# p0b-001.net
KiCad netlist of a schematic drawn in EAGLE
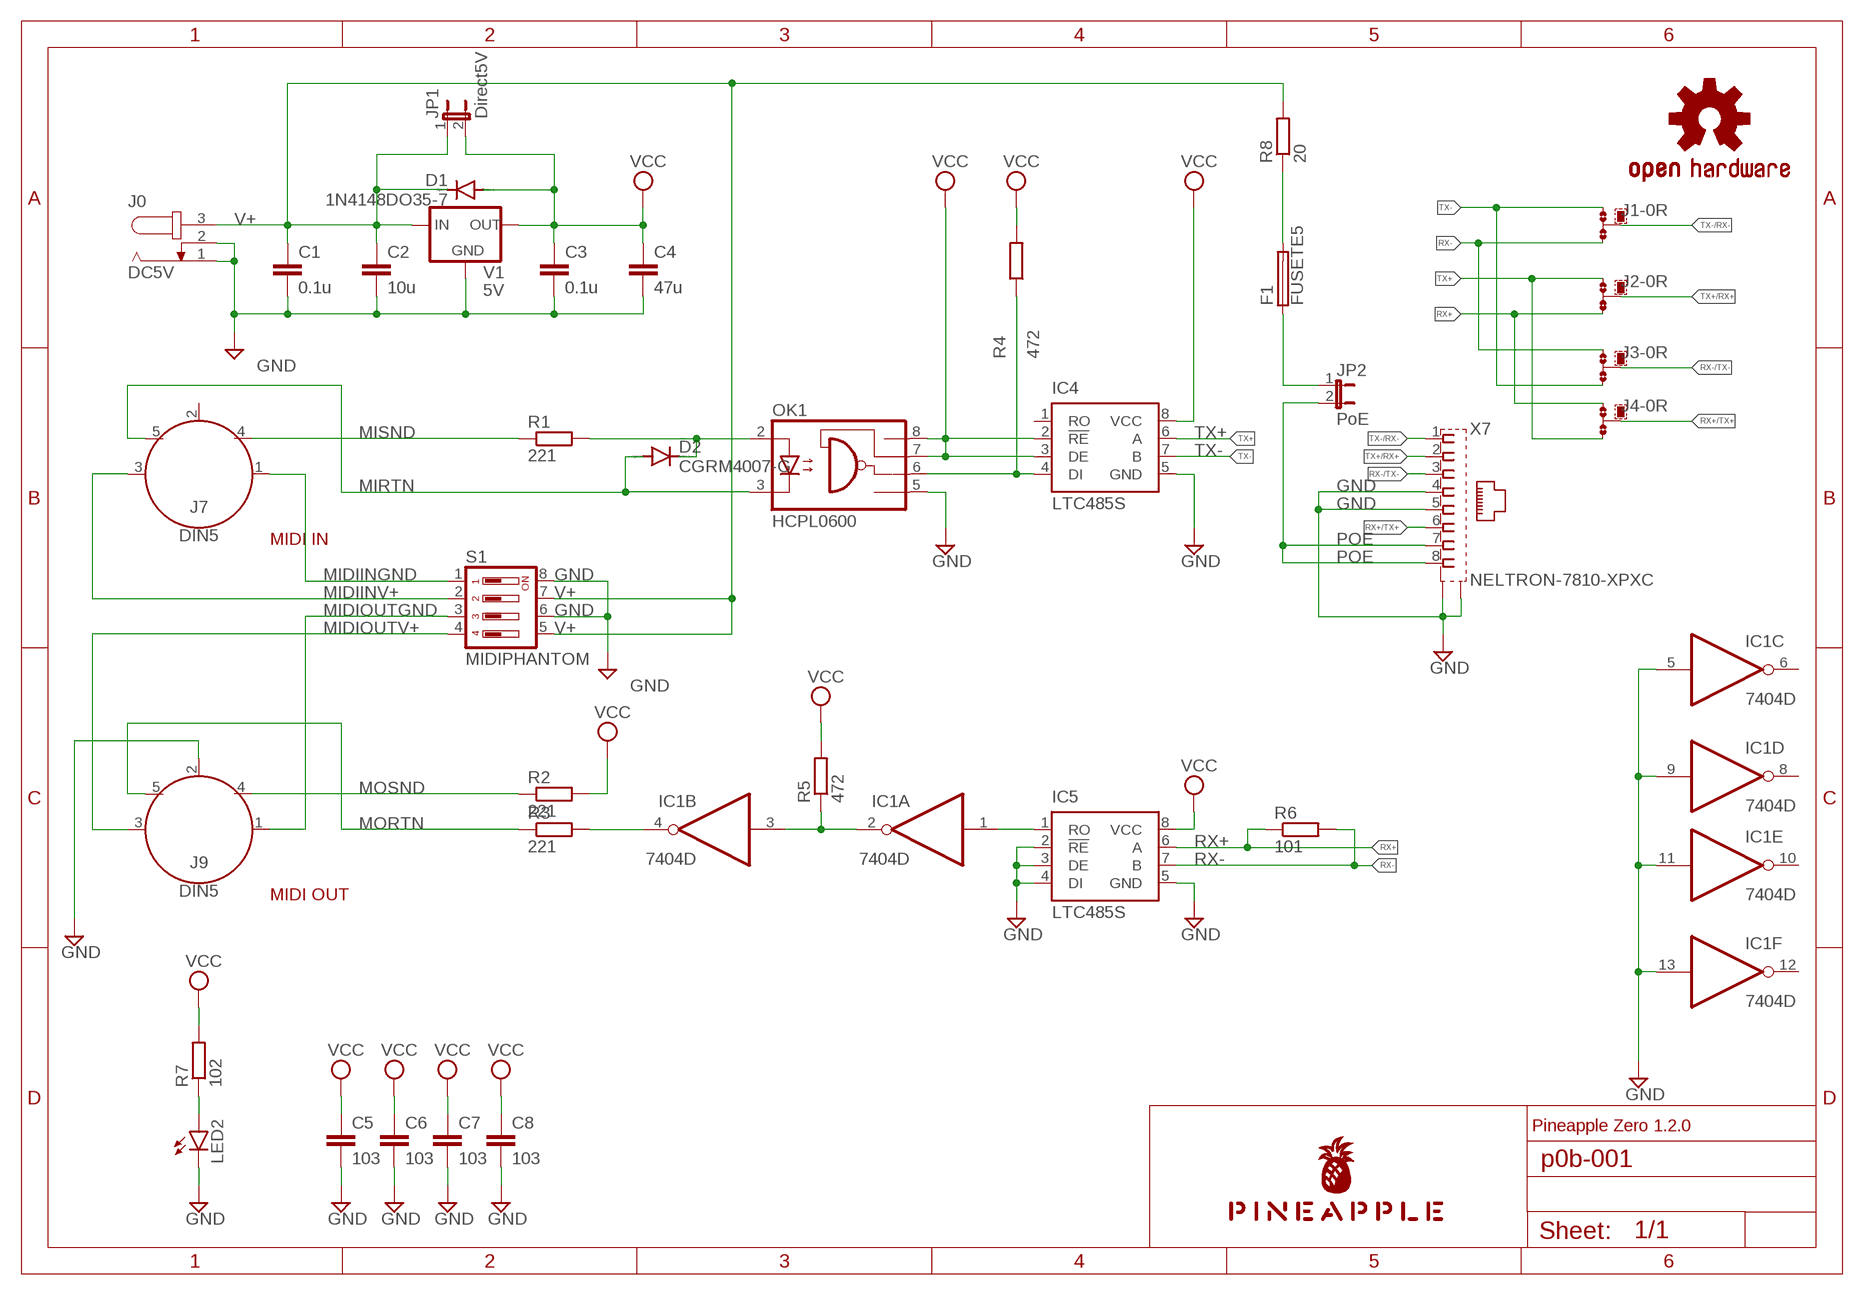
[diagram p0: schematic, sheet 1]

(export (version "E")
  (design (tool "Eeschema 10.0.6"))
  (components
    (comp (ref "C1")
      (value "0.1u")
      (footprint "eagle-import:C025-025X050")
      (libsource (lib "eagle-import") (part "C-EU025-025X050"))
    )
    (comp (ref "C2")
      (value "10u")
      (footprint "eagle-import:C025-030X050")
      (libsource (lib "eagle-import") (part "C-EU025-030X050"))
    )
    (comp (ref "C3")
      (value "0.1u")
      (footprint "eagle-import:C025-025X050")
      (libsource (lib "eagle-import") (part "C-EU025-025X050"))
    )
    (comp (ref "C4")
      (value "47u")
      (footprint "eagle-import:C025-050X050")
      (libsource (lib "eagle-import") (part "C-EU025-050X050"))
    )
    (comp (ref "C5")
      (value "103")
      (footprint "eagle-import:C1206")
      (libsource (lib "eagle-import") (part "C-EUC1206"))
    )
    (comp (ref "C6")
      (value "103")
      (footprint "eagle-import:C1206")
      (libsource (lib "eagle-import") (part "C-EUC1206"))
    )
    (comp (ref "C7")
      (value "103")
      (footprint "eagle-import:C1206")
      (libsource (lib "eagle-import") (part "C-EUC1206"))
    )
    (comp (ref "C8")
      (value "103")
      (footprint "eagle-import:C1206")
      (libsource (lib "eagle-import") (part "C-EUC1206"))
    )
    (comp (ref "D1")
      (value "1N4148DO35-7")
      (footprint "eagle-import:DO35-7")
      (libsource (lib "eagle-import") (part "1N4148DO35-7"))
    )
    (comp (ref "D2")
      (value "CGRM4007-G")
      (footprint "eagle-import:SOD-123_MINI-SMA")
      (libsource (lib "eagle-import") (part "CGRM400-G7"))
    )
    (comp (ref "F1")
      (value "FUSETE5")
      (footprint "eagle-import:TE5")
      (libsource (lib "eagle-import") (part "FUSETE5"))
    )
    (comp (ref "IC1")
      (value "7404D")
      (footprint "eagle-import:SO14")
      (libsource (lib "eagle-import") (part "7404D"))
    )
    (comp (ref "IC4")
      (value "LTC485S")
      (footprint "eagle-import:SOIC8")
      (libsource (lib "eagle-import") (part "LTC485S"))
    )
    (comp (ref "IC5")
      (value "LTC485S")
      (footprint "eagle-import:SOIC8")
      (libsource (lib "eagle-import") (part "LTC485S"))
    )
    (comp (ref "J0")
      (value "DC5V")
      (footprint "eagle-import:SPC4077")
      (libsource (lib "eagle-import") (part "JACK-PLUG0"))
    )
    (comp (ref "J1")
      (value "0R-JUMPA")
      (footprint "eagle-import:A0R-JMP")
      (libsource (lib "eagle-import") (part "0R-JUMPA"))
    )
    (comp (ref "J2")
      (value "0R-JUMPA")
      (footprint "eagle-import:A0R-JMP")
      (libsource (lib "eagle-import") (part "0R-JUMPA"))
    )
    (comp (ref "J3")
      (value "0R-JUMPA")
      (footprint "eagle-import:A0R-JMP")
      (libsource (lib "eagle-import") (part "0R-JUMPA"))
    )
    (comp (ref "J4")
      (value "0R-JUMPA")
      (footprint "eagle-import:A0R-JMP")
      (libsource (lib "eagle-import") (part "0R-JUMPA"))
    )
    (comp (ref "J7")
      (value "DIN5")
      (footprint "eagle-import:DIN5-RA-PTH")
      (libsource (lib "eagle-import") (part "DIN5"))
    )
    (comp (ref "J9")
      (value "DIN5")
      (footprint "eagle-import:DIN5-RA-PTH")
      (libsource (lib "eagle-import") (part "DIN5"))
    )
    (comp (ref "JP1")
      (value "Direct5V")
      (footprint "eagle-import:JP1")
      (libsource (lib "eagle-import") (part "JP1E"))
    )
    (comp (ref "JP2")
      (value "PoE")
      (footprint "eagle-import:JP1")
      (libsource (lib "eagle-import") (part "JP1E"))
    )
    (comp (ref "LED2")
      (value "LEDCHIPLED_1206")
      (footprint "eagle-import:CHIPLED_1206")
      (libsource (lib "eagle-import") (part "LEDCHIPLED_1206"))
    )
    (comp (ref "LOGO1")
      (value "OSHW-LOGOS-COPPER")
      (footprint "eagle-import:OSHW-LOGO-S_COPPER")
      (libsource (lib "eagle-import") (part "OSHW-LOGOS-COPPER"))
    )
    (comp (ref "OK1")
      (value "HCPL0600")
      (footprint "eagle-import:SOIC08")
      (fields (field (name "MF") "AGILENT TECHNOLOGIES") (field (name "MPN") "HCPL-0600-000E"))
      (libsource (lib "eagle-import") (part "HCPL0600"))
    )
    (comp (ref "R1")
      (value "221")
      (footprint "eagle-import:M2012")
      (libsource (lib "eagle-import") (part "R-EU_M2012"))
    )
    (comp (ref "R2")
      (value "221")
      (footprint "eagle-import:M2012")
      (libsource (lib "eagle-import") (part "R-EU_M2012"))
    )
    (comp (ref "R3")
      (value "221")
      (footprint "eagle-import:M2012")
      (libsource (lib "eagle-import") (part "R-EU_M2012"))
    )
    (comp (ref "R4")
      (value "472")
      (footprint "eagle-import:M2012")
      (libsource (lib "eagle-import") (part "R-EU_M2012"))
    )
    (comp (ref "R5")
      (value "472")
      (footprint "eagle-import:M2012")
      (libsource (lib "eagle-import") (part "R-EU_M2012"))
    )
    (comp (ref "R6")
      (value "101")
      (footprint "eagle-import:M2012")
      (libsource (lib "eagle-import") (part "R-EU_M2012"))
    )
    (comp (ref "R7")
      (value "102")
      (footprint "eagle-import:M2012")
      (libsource (lib "eagle-import") (part "R-EU_M2012"))
    )
    (comp (ref "R8")
      (value "20")
      (footprint "eagle-import:0204_5")
      (libsource (lib "eagle-import") (part "R-EU_0204/5"))
    )
    (comp (ref "S1")
      (value "MIDIPHANTOM")
      (footprint "eagle-import:DIP04YL")
      (libsource (lib "eagle-import") (part "DIP04YL"))
    )
    (comp (ref "U$1")
      (value "PINEAPPLE450")
      (footprint "eagle-import:PINEAPPLE450")
      (libsource (lib "eagle-import") (part "PINEAPPLE450"))
    )
    (comp (ref "V1")
      (value "5V")
      (footprint "eagle-import:78XXS")
      (libsource (lib "eagle-import") (part "78XXS"))
    )
    (comp (ref "X7")
      (value "NELTRON-7810-XPXC")
      (footprint "eagle-import:NELTRON-7810-XPXC-FOOTPRINT")
      (libsource (lib "eagle-import") (part "NELTRON-7810-XPXC"))
    )
  )
  (nets
    (net (code "1") (name "/MIDIINGND") (class "Default")
      (node (ref "J7") (pin "1") (pinfunction "1_1") (pintype "bidirectional"))
      (node (ref "S1") (pin "1") (pinfunction "1_1") (pintype "passive"))
    )
    (net (code "2") (name "/MIDIINV+") (class "Default")
      (node (ref "J7") (pin "3") (pinfunction "3_3") (pintype "bidirectional"))
      (node (ref "S1") (pin "2") (pinfunction "2_2") (pintype "passive"))
    )
    (net (code "3") (name "/MIDIOUTGND") (class "Default")
      (node (ref "J9") (pin "1") (pinfunction "1_1") (pintype "bidirectional"))
      (node (ref "S1") (pin "3") (pinfunction "3_3") (pintype "passive"))
    )
    (net (code "4") (name "/MIDIOUTV+") (class "Default")
      (node (ref "J9") (pin "3") (pinfunction "3_3") (pintype "bidirectional"))
      (node (ref "S1") (pin "4") (pinfunction "4_4") (pintype "passive"))
    )
    (net (code "5") (name "/MIRTN") (class "Default")
      (node (ref "D2") (pin "A") (pinfunction "A_A") (pintype "passive"))
      (node (ref "J7") (pin "5") (pinfunction "5_5") (pintype "bidirectional"))
      (node (ref "OK1") (pin "3") (pinfunction "C_3") (pintype "passive"))
    )
    (net (code "6") (name "/MISND") (class "Default")
      (node (ref "J7") (pin "4") (pinfunction "4_4") (pintype "bidirectional"))
      (node (ref "R1") (pin "1") (pinfunction "1_1") (pintype "passive"))
    )
    (net (code "7") (name "/MORTN") (class "Default")
      (node (ref "J9") (pin "5") (pinfunction "5_5") (pintype "bidirectional"))
      (node (ref "R3") (pin "1") (pinfunction "1_1") (pintype "passive"))
    )
    (net (code "8") (name "/MOSND") (class "Default")
      (node (ref "J9") (pin "4") (pinfunction "4_4") (pintype "bidirectional"))
      (node (ref "R2") (pin "1") (pinfunction "1_1") (pintype "passive"))
    )
    (net (code "9") (name "/POE") (class "Default")
      (node (ref "JP2") (pin "2") (pinfunction "2_2") (pintype "passive"))
      (node (ref "X7") (pin "7") (pinfunction "7_7") (pintype "passive"))
      (node (ref "X7") (pin "8") (pinfunction "8_8") (pintype "passive"))
    )
    (net (code "10") (name "/V+") (class "Default")
      (node (ref "C1") (pin "1") (pinfunction "1_1") (pintype "passive"))
      (node (ref "C2") (pin "1") (pinfunction "1_1") (pintype "passive"))
      (node (ref "D1") (pin "C") (pinfunction "C_C") (pintype "passive"))
      (node (ref "J0") (pin "3") (pinfunction "3_3") (pintype "passive"))
      (node (ref "JP1") (pin "1") (pinfunction "1_1") (pintype "passive"))
      (node (ref "R8") (pin "2") (pinfunction "2_2") (pintype "passive"))
      (node (ref "S1") (pin "5") (pinfunction "5_5") (pintype "passive"))
      (node (ref "S1") (pin "7") (pinfunction "7_7") (pintype "passive"))
      (node (ref "V1") (pin "IN") (pinfunction "IN_IN") (pintype "input"))
    )
    (net (code "11") (name "GND") (class "Default")
      (node (ref "C1") (pin "2") (pinfunction "2_2") (pintype "passive"))
      (node (ref "C2") (pin "2") (pinfunction "2_2") (pintype "passive"))
      (node (ref "C3") (pin "2") (pinfunction "2_2") (pintype "passive"))
      (node (ref "C4") (pin "2") (pinfunction "2_2") (pintype "passive"))
      (node (ref "C5") (pin "2") (pinfunction "2_2") (pintype "passive"))
      (node (ref "C6") (pin "2") (pinfunction "2_2") (pintype "passive"))
      (node (ref "C7") (pin "2") (pinfunction "2_2") (pintype "passive"))
      (node (ref "C8") (pin "2") (pinfunction "2_2") (pintype "passive"))
      (node (ref "IC1") (pin "11") (pinfunction "I_11") (pintype "input"))
      (node (ref "IC1") (pin "13") (pinfunction "I_13") (pintype "input"))
      (node (ref "IC1") (pin "5") (pinfunction "I_5") (pintype "input"))
      (node (ref "IC1") (pin "9") (pinfunction "I_9") (pintype "input"))
      (node (ref "IC4") (pin "5") (pinfunction "GND_5") (pintype "input"))
      (node (ref "IC5") (pin "2") (pinfunction "~{RE}_2") (pintype "input"))
      (node (ref "IC5") (pin "3") (pinfunction "DE_3") (pintype "input"))
      (node (ref "IC5") (pin "4") (pinfunction "DI_4") (pintype "input"))
      (node (ref "IC5") (pin "5") (pinfunction "GND_5") (pintype "input"))
      (node (ref "J0") (pin "1") (pinfunction "1_1") (pintype "passive"))
      (node (ref "J0") (pin "2") (pinfunction "2_2") (pintype "passive"))
      (node (ref "J9") (pin "2") (pinfunction "2_2") (pintype "bidirectional"))
      (node (ref "LED2") (pin "C") (pinfunction "C_C") (pintype "passive"))
      (node (ref "OK1") (pin "5") (pinfunction "GND_5") (pintype "passive"))
      (node (ref "S1") (pin "6") (pinfunction "6_6") (pintype "passive"))
      (node (ref "S1") (pin "8") (pinfunction "8_8") (pintype "passive"))
      (node (ref "V1") (pin "GND") (pinfunction "GND_GND") (pintype "input"))
      (node (ref "X7") (pin "4") (pinfunction "4_4") (pintype "passive"))
      (node (ref "X7") (pin "5") (pinfunction "5_5") (pintype "passive"))
      (node (ref "X7") (pin "S1") (pinfunction "S1_S1") (pintype "passive"))
      (node (ref "X7") (pin "S2") (pinfunction "S2_S2") (pintype "passive"))
    )
    (net (code "12") (name "Net-(F1-Pad1)") (class "Default")
      (node (ref "F1") (pin "1") (pinfunction "1_1") (pintype "passive"))
      (node (ref "JP2") (pin "1") (pinfunction "1_1") (pintype "passive"))
    )
    (net (code "13") (name "Net-(F1-Pad2)") (class "Default")
      (node (ref "F1") (pin "2") (pinfunction "2_2") (pintype "passive"))
      (node (ref "R8") (pin "1") (pinfunction "1_1") (pintype "passive"))
    )
    (net (code "14") (name "Net-(IC1A-I)") (class "Default")
      (node (ref "IC1") (pin "1") (pinfunction "I_1") (pintype "input"))
      (node (ref "IC5") (pin "1") (pinfunction "RO_1") (pintype "output"))
    )
    (net (code "15") (name "Net-(IC1A-O)") (class "Default")
      (node (ref "IC1") (pin "2") (pinfunction "O_2") (pintype "output"))
      (node (ref "IC1") (pin "3") (pinfunction "I_3") (pintype "input"))
      (node (ref "R5") (pin "1") (pinfunction "1_1") (pintype "passive"))
    )
    (net (code "16") (name "Net-(IC1B-O)") (class "Default")
      (node (ref "IC1") (pin "4") (pinfunction "O_4") (pintype "output"))
      (node (ref "R3") (pin "2") (pinfunction "2_2") (pintype "passive"))
    )
    (net (code "17") (name "Net-(IC4-DI)") (class "Default")
      (node (ref "IC4") (pin "4") (pinfunction "DI_4") (pintype "input"))
      (node (ref "OK1") (pin "6") (pinfunction "VO_6") (pintype "passive"))
      (node (ref "R4") (pin "1") (pinfunction "1_1") (pintype "passive"))
    )
    (net (code "18") (name "Net-(LED2-PadA)") (class "Default")
      (node (ref "LED2") (pin "A") (pinfunction "A_A") (pintype "passive"))
      (node (ref "R7") (pin "1") (pinfunction "1_1") (pintype "passive"))
    )
    (net (code "19") (name "Net-(OK1-A)") (class "Default")
      (node (ref "D2") (pin "C") (pinfunction "C_C") (pintype "passive"))
      (node (ref "OK1") (pin "2") (pinfunction "A_2") (pintype "passive"))
      (node (ref "R1") (pin "2") (pinfunction "2_2") (pintype "passive"))
    )
    (net (code "20") (name "RX+") (class "Default")
      (node (ref "IC5") (pin "6") (pinfunction "A_6") (pintype "bidirectional"))
      (node (ref "J2") (pin "3") (pinfunction "3_3") (pintype "passive"))
      (node (ref "J4") (pin "1") (pinfunction "1_1") (pintype "passive"))
      (node (ref "R6") (pin "1") (pinfunction "1_1") (pintype "passive"))
    )
    (net (code "21") (name "RX+{slash}TX+") (class "Default")
      (node (ref "J4") (pin "2") (pinfunction "2_2") (pintype "passive"))
      (node (ref "X7") (pin "6") (pinfunction "6_6") (pintype "passive"))
    )
    (net (code "22") (name "RX-") (class "Default")
      (node (ref "IC5") (pin "7") (pinfunction "B_7") (pintype "bidirectional"))
      (node (ref "J1") (pin "3") (pinfunction "3_3") (pintype "passive"))
      (node (ref "J3") (pin "1") (pinfunction "1_1") (pintype "passive"))
      (node (ref "R6") (pin "2") (pinfunction "2_2") (pintype "passive"))
    )
    (net (code "23") (name "RX-{slash}TX-") (class "Default")
      (node (ref "J3") (pin "2") (pinfunction "2_2") (pintype "passive"))
      (node (ref "X7") (pin "3") (pinfunction "3_3") (pintype "passive"))
    )
    (net (code "24") (name "TX+") (class "Default")
      (node (ref "IC4") (pin "6") (pinfunction "A_6") (pintype "bidirectional"))
      (node (ref "J2") (pin "1") (pinfunction "1_1") (pintype "passive"))
      (node (ref "J4") (pin "3") (pinfunction "3_3") (pintype "passive"))
    )
    (net (code "25") (name "TX+{slash}RX+") (class "Default")
      (node (ref "J2") (pin "2") (pinfunction "2_2") (pintype "passive"))
      (node (ref "X7") (pin "2") (pinfunction "2_2") (pintype "passive"))
    )
    (net (code "26") (name "TX-") (class "Default")
      (node (ref "IC4") (pin "7") (pinfunction "B_7") (pintype "bidirectional"))
      (node (ref "J1") (pin "1") (pinfunction "1_1") (pintype "passive"))
      (node (ref "J3") (pin "3") (pinfunction "3_3") (pintype "passive"))
    )
    (net (code "27") (name "TX-{slash}RX-") (class "Default")
      (node (ref "J1") (pin "2") (pinfunction "2_2") (pintype "passive"))
      (node (ref "X7") (pin "1") (pinfunction "1_1") (pintype "passive"))
    )
    (net (code "28") (name "VCC") (class "Default")
      (node (ref "C3") (pin "1") (pinfunction "1_1") (pintype "passive"))
      (node (ref "C4") (pin "1") (pinfunction "1_1") (pintype "passive"))
      (node (ref "C5") (pin "1") (pinfunction "1_1") (pintype "passive"))
      (node (ref "C6") (pin "1") (pinfunction "1_1") (pintype "passive"))
      (node (ref "C7") (pin "1") (pinfunction "1_1") (pintype "passive"))
      (node (ref "C8") (pin "1") (pinfunction "1_1") (pintype "passive"))
      (node (ref "D1") (pin "A") (pinfunction "A_A") (pintype "passive"))
      (node (ref "IC4") (pin "2") (pinfunction "~{RE}_2") (pintype "input"))
      (node (ref "IC4") (pin "3") (pinfunction "DE_3") (pintype "input"))
      (node (ref "IC4") (pin "8") (pinfunction "VCC_8") (pintype "input"))
      (node (ref "IC5") (pin "8") (pinfunction "VCC_8") (pintype "input"))
      (node (ref "JP1") (pin "2") (pinfunction "2_2") (pintype "passive"))
      (node (ref "OK1") (pin "7") (pinfunction "VE_7") (pintype "passive"))
      (node (ref "OK1") (pin "8") (pinfunction "VCC_8") (pintype "passive"))
      (node (ref "R2") (pin "2") (pinfunction "2_2") (pintype "passive"))
      (node (ref "R4") (pin "2") (pinfunction "2_2") (pintype "passive"))
      (node (ref "R5") (pin "2") (pinfunction "2_2") (pintype "passive"))
      (node (ref "R7") (pin "2") (pinfunction "2_2") (pintype "passive"))
      (node (ref "V1") (pin "OUT") (pinfunction "OUT_OUT") (pintype "passive"))
    )
    (net (code "29") (name "unconnected-(IC1C-O-Pad6)") (class "Default")
      (node (ref "IC1") (pin "6") (pinfunction "O_6") (pintype "output"))
    )
    (net (code "30") (name "unconnected-(IC1D-O-Pad8)") (class "Default")
      (node (ref "IC1") (pin "8") (pinfunction "O_8") (pintype "output"))
    )
    (net (code "31") (name "unconnected-(IC1E-O-Pad10)") (class "Default")
      (node (ref "IC1") (pin "10") (pinfunction "O_10") (pintype "output"))
    )
    (net (code "32") (name "unconnected-(IC1F-O-Pad12)") (class "Default")
      (node (ref "IC1") (pin "12") (pinfunction "O_12") (pintype "output"))
    )
    (net (code "33") (name "unconnected-(IC4-RO-Pad1)") (class "Default")
      (node (ref "IC4") (pin "1") (pinfunction "RO_1") (pintype "output"))
    )
    (net (code "34") (name "unconnected-(J7-Pad2)") (class "Default")
      (node (ref "J7") (pin "2") (pinfunction "2_2") (pintype "bidirectional"))
    )
  )
)
